# apollobvm_pcb.net
KiCad netlist of a schematic drawn in EAGLE
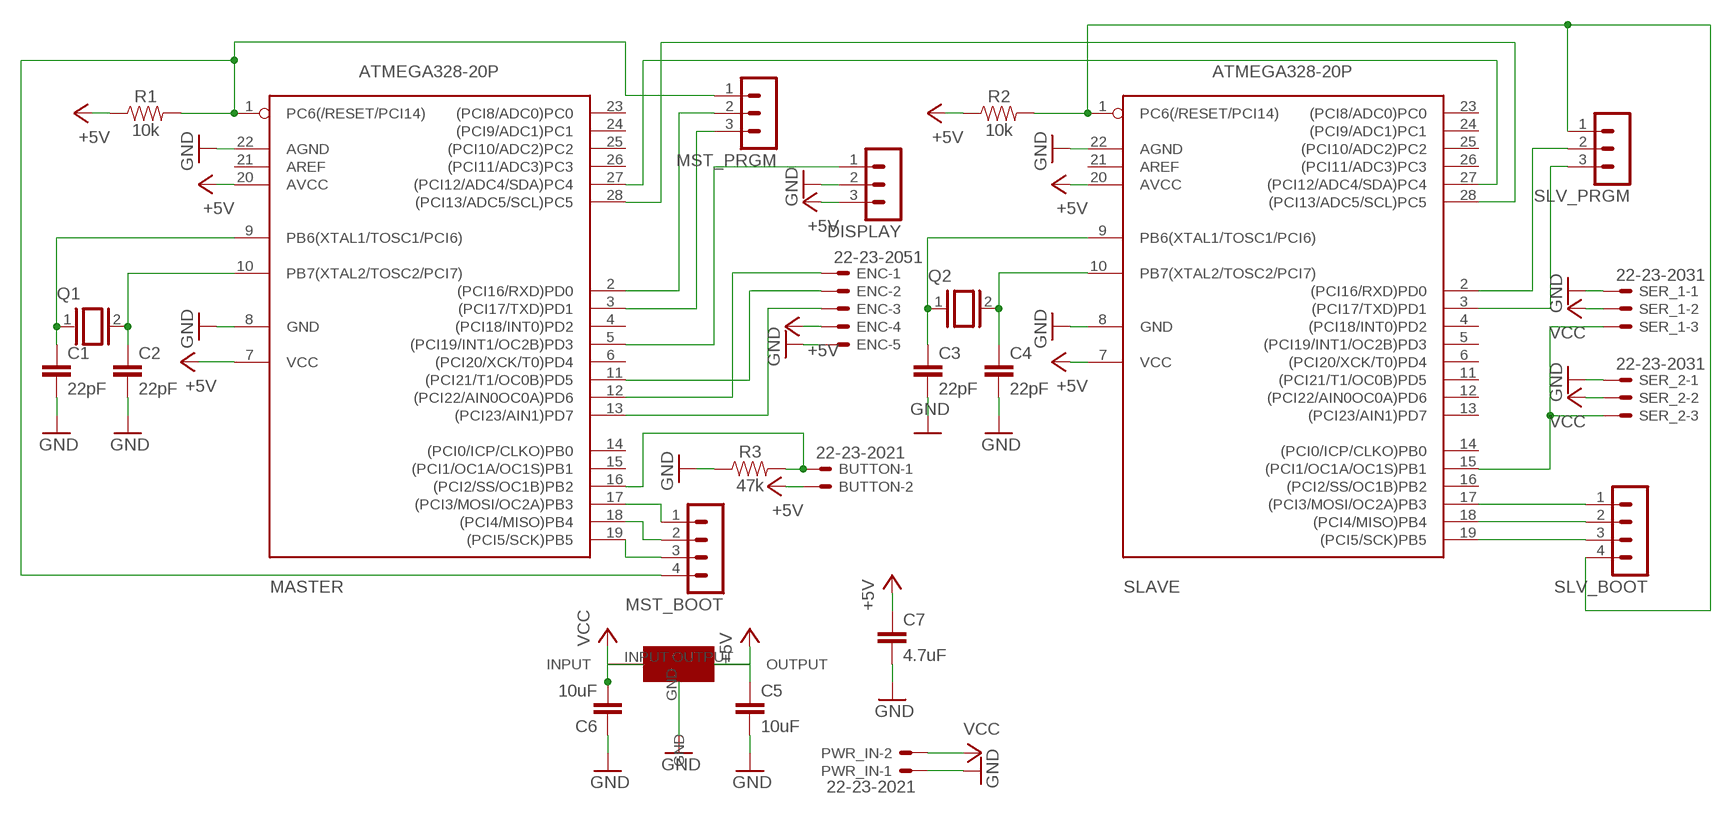
[diagram p0: schematic, sheet 1]

(export (version "E")
  (design (tool "Eeschema 10.0.6"))
  (components
    (comp (ref "BUTTON")
      (value "22-23-2021")
      (footprint "eagle-import:22-23-2021")
      (fields (field (name "MF") "MOLEX"))
      (libsource (lib "eagle-import") (part "22-23-2021"))
    )
    (comp (ref "C1")
      (value "22pF")
      (footprint "eagle-import:0603")
      (libsource (lib "eagle-import") (part "22PF-0603-50V-5%"))
    )
    (comp (ref "C2")
      (value "22pF")
      (footprint "eagle-import:0603")
      (libsource (lib "eagle-import") (part "22PF-0603-50V-5%"))
    )
    (comp (ref "C3")
      (value "22pF")
      (footprint "eagle-import:0603")
      (libsource (lib "eagle-import") (part "22PF-0603-50V-5%"))
    )
    (comp (ref "C4")
      (value "22pF")
      (footprint "eagle-import:0603")
      (libsource (lib "eagle-import") (part "22PF-0603-50V-5%"))
    )
    (comp (ref "C5")
      (value "10uF")
      (footprint "eagle-import:0603")
      (libsource (lib "eagle-import") (part "10UF-0603-6.3V-20%"))
    )
    (comp (ref "C6")
      (value "10uF")
      (footprint "eagle-import:0603")
      (libsource (lib "eagle-import") (part "10UF-0603-6.3V-20%"))
    )
    (comp (ref "C7")
      (value "4.7uF")
      (footprint "eagle-import:0603")
      (libsource (lib "eagle-import") (part "4.7UF0603"))
    )
    (comp (ref "DISPLAY")
      (value "MA03-1")
      (footprint "eagle-import:MA03-1")
      (libsource (lib "eagle-import") (part "MA03-1"))
    )
    (comp (ref "ENC")
      (value "22-23-2051")
      (footprint "eagle-import:22-23-2051")
      (fields (field (name "MF") "MOLEX"))
      (libsource (lib "eagle-import") (part "22-23-2051"))
    )
    (comp (ref "MASTER")
      (value "ATMEGA328-20P")
      (footprint "eagle-import:DIL28-3")
      (libsource (lib "eagle-import") (part "ATMEGA328P-20"))
    )
    (comp (ref "MST_BOOT")
      (value "MA04-1")
      (footprint "eagle-import:MA04-1")
      (libsource (lib "eagle-import") (part "MA04-1"))
    )
    (comp (ref "MST_PRGM")
      (value "MA03-1")
      (footprint "eagle-import:MA03-1")
      (libsource (lib "eagle-import") (part "MA03-1"))
    )
    (comp (ref "PWR_IN")
      (value "22-23-2021")
      (footprint "eagle-import:22-23-2021")
      (fields (field (name "MF") "MOLEX"))
      (libsource (lib "eagle-import") (part "22-23-2021"))
    )
    (comp (ref "Q1")
      (value "XTAL/S")
      (footprint "eagle-import:QS")
      (libsource (lib "eagle-import") (part "XTAL/S"))
    )
    (comp (ref "Q2")
      (value "XTAL/S")
      (footprint "eagle-import:QS")
      (libsource (lib "eagle-import") (part "XTAL/S"))
    )
    (comp (ref "R1")
      (value "10k")
      (footprint "eagle-import:0603")
      (libsource (lib "eagle-import") (part "10KOHM-0603-1/10W-1%"))
    )
    (comp (ref "R2")
      (value "10k")
      (footprint "eagle-import:0603")
      (libsource (lib "eagle-import") (part "10KOHM-0603-1/10W-1%"))
    )
    (comp (ref "R3")
      (value "47k")
      (footprint "eagle-import:0603")
      (libsource (lib "eagle-import") (part "47KOHM-0603-1/10W-1%"))
    )
    (comp (ref "SER_1")
      (value "22-23-2031")
      (footprint "eagle-import:22-23-2031")
      (fields (field (name "MF") "MOLEX"))
      (libsource (lib "eagle-import") (part "22-23-2031"))
    )
    (comp (ref "SER_2")
      (value "22-23-2031")
      (footprint "eagle-import:22-23-2031")
      (fields (field (name "MF") "MOLEX"))
      (libsource (lib "eagle-import") (part "22-23-2031"))
    )
    (comp (ref "SLAVE")
      (value "ATMEGA328-20P")
      (footprint "eagle-import:DIL28-3")
      (libsource (lib "eagle-import") (part "ATMEGA328P-20"))
    )
    (comp (ref "SLV_BOOT")
      (value "MA04-1")
      (footprint "eagle-import:MA04-1")
      (libsource (lib "eagle-import") (part "MA04-1"))
    )
    (comp (ref "SLV_PRGM")
      (value "MA03-1")
      (footprint "eagle-import:MA03-1")
      (libsource (lib "eagle-import") (part "MA03-1"))
    )
    (comp (ref "U$1")
      (value "NCP1117")
      (footprint "eagle-import:NCP1117")
      (libsource (lib "eagle-import") (part "NCP1117"))
    )
  )
  (nets
    (net (code "1") (name "+5V") (class "Default")
      (node (ref "BUTTON") (pin "2") (pinfunction "S_2") (pintype "passive"))
      (node (ref "C5") (pin "1") (pinfunction "1_1") (pintype "passive"))
      (node (ref "C7") (pin "1") (pinfunction "1_1") (pintype "passive"))
      (node (ref "DISPLAY") (pin "3") (pinfunction "3_3") (pintype "passive"))
      (node (ref "ENC") (pin "4") (pinfunction "S_4") (pintype "passive"))
      (node (ref "MASTER") (pin "20") (pinfunction "AVCC_20") (pintype "bidirectional"))
      (node (ref "MASTER") (pin "7") (pinfunction "VCC_7") (pintype "bidirectional"))
      (node (ref "R1") (pin "1") (pinfunction "1_1") (pintype "passive"))
      (node (ref "R2") (pin "1") (pinfunction "1_1") (pintype "passive"))
      (node (ref "SLAVE") (pin "20") (pinfunction "AVCC_20") (pintype "bidirectional"))
      (node (ref "SLAVE") (pin "7") (pinfunction "VCC_7") (pintype "bidirectional"))
      (node (ref "U$1") (pin "OUTPUT") (pinfunction "OUTPUT_OUTPUT") (pintype "bidirectional"))
    )
    (net (code "2") (name "GND") (class "Default")
      (node (ref "C1") (pin "2") (pinfunction "2_2") (pintype "passive"))
      (node (ref "C2") (pin "2") (pinfunction "2_2") (pintype "passive"))
      (node (ref "C3") (pin "2") (pinfunction "2_2") (pintype "passive"))
      (node (ref "C4") (pin "2") (pinfunction "2_2") (pintype "passive"))
      (node (ref "C5") (pin "2") (pinfunction "2_2") (pintype "passive"))
      (node (ref "C6") (pin "1") (pinfunction "1_1") (pintype "passive"))
      (node (ref "C7") (pin "2") (pinfunction "2_2") (pintype "passive"))
      (node (ref "DISPLAY") (pin "2") (pinfunction "2_2") (pintype "passive"))
      (node (ref "ENC") (pin "5") (pinfunction "S_5") (pintype "passive"))
      (node (ref "MASTER") (pin "22") (pinfunction "AGND_22") (pintype "bidirectional"))
      (node (ref "MASTER") (pin "8") (pinfunction "GND_8") (pintype "bidirectional"))
      (node (ref "PWR_IN") (pin "1") (pinfunction "S_1") (pintype "passive"))
      (node (ref "R3") (pin "1") (pinfunction "1_1") (pintype "passive"))
      (node (ref "SER_1") (pin "1") (pinfunction "S_1") (pintype "passive"))
      (node (ref "SER_2") (pin "1") (pinfunction "S_1") (pintype "passive"))
      (node (ref "SLAVE") (pin "22") (pinfunction "AGND_22") (pintype "bidirectional"))
      (node (ref "SLAVE") (pin "8") (pinfunction "GND_8") (pintype "bidirectional"))
      (node (ref "U$1") (pin "GND") (pinfunction "GND_GND") (pintype "bidirectional"))
    )
    (net (code "3") (name "Net-(BUTTONA-S)") (class "Default")
      (node (ref "BUTTON") (pin "1") (pinfunction "S_1") (pintype "passive"))
      (node (ref "MASTER") (pin "16") (pinfunction "(PCI2/SS/OC1B)PB2_16") (pintype "bidirectional"))
      (node (ref "R3") (pin "2") (pinfunction "2_2") (pintype "passive"))
    )
    (net (code "4") (name "Net-(ENCA-S)") (class "Default")
      (node (ref "ENC") (pin "1") (pinfunction "S_1") (pintype "passive"))
      (node (ref "MASTER") (pin "12") (pinfunction "(PCI22/AIN0OC0A)PD6_12") (pintype "bidirectional"))
    )
    (net (code "5") (name "Net-(ENCB-S)") (class "Default")
      (node (ref "ENC") (pin "2") (pinfunction "S_2") (pintype "passive"))
      (node (ref "MASTER") (pin "11") (pinfunction "(PCI21/T1/OC0B)PD5_11") (pintype "bidirectional"))
    )
    (net (code "6") (name "Net-(ENCC-S)") (class "Default")
      (node (ref "ENC") (pin "3") (pinfunction "S_3") (pintype "passive"))
      (node (ref "MASTER") (pin "13") (pinfunction "(PCI23/AIN1)PD7_13") (pintype "bidirectional"))
    )
    (net (code "7") (name "Net-(MASTER-(PCI3{slash}MOSI{slash}OC2A)PB3)") (class "Default")
      (node (ref "MASTER") (pin "17") (pinfunction "(PCI3/MOSI/OC2A)PB3_17") (pintype "bidirectional"))
      (node (ref "MST_BOOT") (pin "1") (pinfunction "1_1") (pintype "passive"))
    )
    (net (code "8") (name "Net-(MASTER-(PCI4{slash}MISO)PB4)") (class "Default")
      (node (ref "MASTER") (pin "18") (pinfunction "(PCI4/MISO)PB4_18") (pintype "bidirectional"))
      (node (ref "MST_BOOT") (pin "2") (pinfunction "2_2") (pintype "passive"))
    )
    (net (code "9") (name "Net-(MASTER-(PCI5{slash}SCK)PB5)") (class "Default")
      (node (ref "MASTER") (pin "19") (pinfunction "(PCI5/SCK)PB5_19") (pintype "bidirectional"))
      (node (ref "MST_BOOT") (pin "3") (pinfunction "3_3") (pintype "passive"))
    )
    (net (code "10") (name "Net-(MASTER-(PCI12{slash}ADC4{slash}SDA)PC4)") (class "Default")
      (node (ref "MASTER") (pin "27") (pinfunction "(PCI12/ADC4/SDA)PC4_27") (pintype "bidirectional"))
      (node (ref "SLAVE") (pin "27") (pinfunction "(PCI12/ADC4/SDA)PC4_27") (pintype "bidirectional"))
    )
    (net (code "11") (name "Net-(MASTER-(PCI13{slash}ADC5{slash}SCL)PC5)") (class "Default")
      (node (ref "MASTER") (pin "28") (pinfunction "(PCI13/ADC5/SCL)PC5_28") (pintype "bidirectional"))
      (node (ref "SLAVE") (pin "28") (pinfunction "(PCI13/ADC5/SCL)PC5_28") (pintype "bidirectional"))
    )
    (net (code "12") (name "Net-(MASTER-(PCI16{slash}RXD)PD0)") (class "Default")
      (node (ref "MASTER") (pin "2") (pinfunction "(PCI16/RXD)PD0_2") (pintype "bidirectional"))
      (node (ref "MST_PRGM") (pin "2") (pinfunction "2_2") (pintype "passive"))
    )
    (net (code "13") (name "Net-(MASTER-(PCI17{slash}TXD)PD1)") (class "Default")
      (node (ref "MASTER") (pin "3") (pinfunction "(PCI17/TXD)PD1_3") (pintype "bidirectional"))
      (node (ref "MST_PRGM") (pin "3") (pinfunction "3_3") (pintype "passive"))
    )
    (net (code "14") (name "Net-(MASTER-(PCI19{slash}INT1{slash}OC2B)PD3)") (class "Default")
      (node (ref "DISPLAY") (pin "1") (pinfunction "1_1") (pintype "passive"))
      (node (ref "MASTER") (pin "5") (pinfunction "(PCI19/INT1/OC2B)PD3_5") (pintype "bidirectional"))
    )
    (net (code "15") (name "Net-(MASTER-PB6(XTAL1{slash}TOSC1{slash}PCI6))") (class "Default")
      (node (ref "C1") (pin "1") (pinfunction "1_1") (pintype "passive"))
      (node (ref "MASTER") (pin "9") (pinfunction "PB6(XTAL1/TOSC1/PCI6)_9") (pintype "bidirectional"))
      (node (ref "Q1") (pin "1") (pinfunction "1_1") (pintype "passive"))
    )
    (net (code "16") (name "Net-(MASTER-PB7(XTAL2{slash}TOSC2{slash}PCI7))") (class "Default")
      (node (ref "C2") (pin "1") (pinfunction "1_1") (pintype "passive"))
      (node (ref "MASTER") (pin "10") (pinfunction "PB7(XTAL2/TOSC2/PCI7)_10") (pintype "bidirectional"))
      (node (ref "Q1") (pin "2") (pinfunction "2_2") (pintype "passive"))
    )
    (net (code "17") (name "Net-(MASTER-PC6({slash}RESET{slash}PCI14))") (class "Default")
      (node (ref "MASTER") (pin "1") (pinfunction "PC6(/RESET/PCI14)_1") (pintype "bidirectional"))
      (node (ref "MST_BOOT") (pin "4") (pinfunction "4_4") (pintype "passive"))
      (node (ref "MST_PRGM") (pin "1") (pinfunction "1_1") (pintype "passive"))
      (node (ref "R1") (pin "2") (pinfunction "2_2") (pintype "passive"))
    )
    (net (code "18") (name "Net-(SER_1C-S)") (class "Default")
      (node (ref "SER_1") (pin "3") (pinfunction "S_3") (pintype "passive"))
      (node (ref "SER_2") (pin "3") (pinfunction "S_3") (pintype "passive"))
      (node (ref "SLAVE") (pin "15") (pinfunction "(PCI1/OC1A/OC1S)PB1_15") (pintype "bidirectional"))
    )
    (net (code "19") (name "Net-(SLAVE-(PCI3{slash}MOSI{slash}OC2A)PB3)") (class "Default")
      (node (ref "SLAVE") (pin "17") (pinfunction "(PCI3/MOSI/OC2A)PB3_17") (pintype "bidirectional"))
      (node (ref "SLV_BOOT") (pin "1") (pinfunction "1_1") (pintype "passive"))
    )
    (net (code "20") (name "Net-(SLAVE-(PCI4{slash}MISO)PB4)") (class "Default")
      (node (ref "SLAVE") (pin "18") (pinfunction "(PCI4/MISO)PB4_18") (pintype "bidirectional"))
      (node (ref "SLV_BOOT") (pin "2") (pinfunction "2_2") (pintype "passive"))
    )
    (net (code "21") (name "Net-(SLAVE-(PCI5{slash}SCK)PB5)") (class "Default")
      (node (ref "SLAVE") (pin "19") (pinfunction "(PCI5/SCK)PB5_19") (pintype "bidirectional"))
      (node (ref "SLV_BOOT") (pin "3") (pinfunction "3_3") (pintype "passive"))
    )
    (net (code "22") (name "Net-(SLAVE-(PCI16{slash}RXD)PD0)") (class "Default")
      (node (ref "SLAVE") (pin "2") (pinfunction "(PCI16/RXD)PD0_2") (pintype "bidirectional"))
      (node (ref "SLV_PRGM") (pin "2") (pinfunction "2_2") (pintype "passive"))
    )
    (net (code "23") (name "Net-(SLAVE-(PCI17{slash}TXD)PD1)") (class "Default")
      (node (ref "SLAVE") (pin "3") (pinfunction "(PCI17/TXD)PD1_3") (pintype "bidirectional"))
      (node (ref "SLV_PRGM") (pin "3") (pinfunction "3_3") (pintype "passive"))
    )
    (net (code "24") (name "Net-(SLAVE-PB6(XTAL1{slash}TOSC1{slash}PCI6))") (class "Default")
      (node (ref "C3") (pin "1") (pinfunction "1_1") (pintype "passive"))
      (node (ref "Q2") (pin "1") (pinfunction "1_1") (pintype "passive"))
      (node (ref "SLAVE") (pin "9") (pinfunction "PB6(XTAL1/TOSC1/PCI6)_9") (pintype "bidirectional"))
    )
    (net (code "25") (name "Net-(SLAVE-PB7(XTAL2{slash}TOSC2{slash}PCI7))") (class "Default")
      (node (ref "C4") (pin "1") (pinfunction "1_1") (pintype "passive"))
      (node (ref "Q2") (pin "2") (pinfunction "2_2") (pintype "passive"))
      (node (ref "SLAVE") (pin "10") (pinfunction "PB7(XTAL2/TOSC2/PCI7)_10") (pintype "bidirectional"))
    )
    (net (code "26") (name "Net-(SLAVE-PC6({slash}RESET{slash}PCI14))") (class "Default")
      (node (ref "R2") (pin "2") (pinfunction "2_2") (pintype "passive"))
      (node (ref "SLAVE") (pin "1") (pinfunction "PC6(/RESET/PCI14)_1") (pintype "bidirectional"))
      (node (ref "SLV_BOOT") (pin "4") (pinfunction "4_4") (pintype "passive"))
      (node (ref "SLV_PRGM") (pin "1") (pinfunction "1_1") (pintype "passive"))
    )
    (net (code "27") (name "VCC") (class "Default")
      (node (ref "C6") (pin "2") (pinfunction "2_2") (pintype "passive"))
      (node (ref "PWR_IN") (pin "2") (pinfunction "S_2") (pintype "passive"))
      (node (ref "SER_1") (pin "2") (pinfunction "S_2") (pintype "passive"))
      (node (ref "SER_2") (pin "2") (pinfunction "S_2") (pintype "passive"))
      (node (ref "U$1") (pin "INPUT") (pinfunction "INPUT_INPUT") (pintype "bidirectional"))
    )
    (net (code "28") (name "unconnected-(MASTER-(PCI0{slash}ICP{slash}CLKO)PB0-Pad14)") (class "Default")
      (node (ref "MASTER") (pin "14") (pinfunction "(PCI0/ICP/CLKO)PB0_14") (pintype "bidirectional"))
    )
    (net (code "29") (name "unconnected-(MASTER-(PCI1{slash}OC1A{slash}OC1S)PB1-Pad15)") (class "Default")
      (node (ref "MASTER") (pin "15") (pinfunction "(PCI1/OC1A/OC1S)PB1_15") (pintype "bidirectional"))
    )
    (net (code "30") (name "unconnected-(MASTER-(PCI8{slash}ADC0)PC0-Pad23)") (class "Default")
      (node (ref "MASTER") (pin "23") (pinfunction "(PCI8/ADC0)PC0_23") (pintype "bidirectional"))
    )
    (net (code "31") (name "unconnected-(MASTER-(PCI9{slash}ADC1)PC1-Pad24)") (class "Default")
      (node (ref "MASTER") (pin "24") (pinfunction "(PCI9/ADC1)PC1_24") (pintype "bidirectional"))
    )
    (net (code "32") (name "unconnected-(MASTER-(PCI10{slash}ADC2)PC2-Pad25)") (class "Default")
      (node (ref "MASTER") (pin "25") (pinfunction "(PCI10/ADC2)PC2_25") (pintype "bidirectional"))
    )
    (net (code "33") (name "unconnected-(MASTER-(PCI11{slash}ADC3)PC3-Pad26)") (class "Default")
      (node (ref "MASTER") (pin "26") (pinfunction "(PCI11/ADC3)PC3_26") (pintype "bidirectional"))
    )
    (net (code "34") (name "unconnected-(MASTER-(PCI18{slash}INT0)PD2-Pad4)") (class "Default")
      (node (ref "MASTER") (pin "4") (pinfunction "(PCI18/INT0)PD2_4") (pintype "bidirectional"))
    )
    (net (code "35") (name "unconnected-(MASTER-(PCI20{slash}XCK{slash}T0)PD4-Pad6)") (class "Default")
      (node (ref "MASTER") (pin "6") (pinfunction "(PCI20/XCK/T0)PD4_6") (pintype "bidirectional"))
    )
    (net (code "36") (name "unconnected-(MASTER-AREF-Pad21)") (class "Default")
      (node (ref "MASTER") (pin "21") (pinfunction "AREF_21") (pintype "bidirectional"))
    )
    (net (code "37") (name "unconnected-(SLAVE-(PCI0{slash}ICP{slash}CLKO)PB0-Pad14)") (class "Default")
      (node (ref "SLAVE") (pin "14") (pinfunction "(PCI0/ICP/CLKO)PB0_14") (pintype "bidirectional"))
    )
    (net (code "38") (name "unconnected-(SLAVE-(PCI2{slash}SS{slash}OC1B)PB2-Pad16)") (class "Default")
      (node (ref "SLAVE") (pin "16") (pinfunction "(PCI2/SS/OC1B)PB2_16") (pintype "bidirectional"))
    )
    (net (code "39") (name "unconnected-(SLAVE-(PCI8{slash}ADC0)PC0-Pad23)") (class "Default")
      (node (ref "SLAVE") (pin "23") (pinfunction "(PCI8/ADC0)PC0_23") (pintype "bidirectional"))
    )
    (net (code "40") (name "unconnected-(SLAVE-(PCI9{slash}ADC1)PC1-Pad24)") (class "Default")
      (node (ref "SLAVE") (pin "24") (pinfunction "(PCI9/ADC1)PC1_24") (pintype "bidirectional"))
    )
    (net (code "41") (name "unconnected-(SLAVE-(PCI10{slash}ADC2)PC2-Pad25)") (class "Default")
      (node (ref "SLAVE") (pin "25") (pinfunction "(PCI10/ADC2)PC2_25") (pintype "bidirectional"))
    )
    (net (code "42") (name "unconnected-(SLAVE-(PCI11{slash}ADC3)PC3-Pad26)") (class "Default")
      (node (ref "SLAVE") (pin "26") (pinfunction "(PCI11/ADC3)PC3_26") (pintype "bidirectional"))
    )
    (net (code "43") (name "unconnected-(SLAVE-(PCI18{slash}INT0)PD2-Pad4)") (class "Default")
      (node (ref "SLAVE") (pin "4") (pinfunction "(PCI18/INT0)PD2_4") (pintype "bidirectional"))
    )
    (net (code "44") (name "unconnected-(SLAVE-(PCI19{slash}INT1{slash}OC2B)PD3-Pad5)") (class "Default")
      (node (ref "SLAVE") (pin "5") (pinfunction "(PCI19/INT1/OC2B)PD3_5") (pintype "bidirectional"))
    )
    (net (code "45") (name "unconnected-(SLAVE-(PCI20{slash}XCK{slash}T0)PD4-Pad6)") (class "Default")
      (node (ref "SLAVE") (pin "6") (pinfunction "(PCI20/XCK/T0)PD4_6") (pintype "bidirectional"))
    )
    (net (code "46") (name "unconnected-(SLAVE-(PCI21{slash}T1{slash}OC0B)PD5-Pad11)") (class "Default")
      (node (ref "SLAVE") (pin "11") (pinfunction "(PCI21/T1/OC0B)PD5_11") (pintype "bidirectional"))
    )
    (net (code "47") (name "unconnected-(SLAVE-(PCI22{slash}AIN0OC0A)PD6-Pad12)") (class "Default")
      (node (ref "SLAVE") (pin "12") (pinfunction "(PCI22/AIN0OC0A)PD6_12") (pintype "bidirectional"))
    )
    (net (code "48") (name "unconnected-(SLAVE-(PCI23{slash}AIN1)PD7-Pad13)") (class "Default")
      (node (ref "SLAVE") (pin "13") (pinfunction "(PCI23/AIN1)PD7_13") (pintype "bidirectional"))
    )
    (net (code "49") (name "unconnected-(SLAVE-AREF-Pad21)") (class "Default")
      (node (ref "SLAVE") (pin "21") (pinfunction "AREF_21") (pintype "bidirectional"))
    )
  )
)
